# 12706.net
KiCad netlist of a schematic drawn in EAGLE
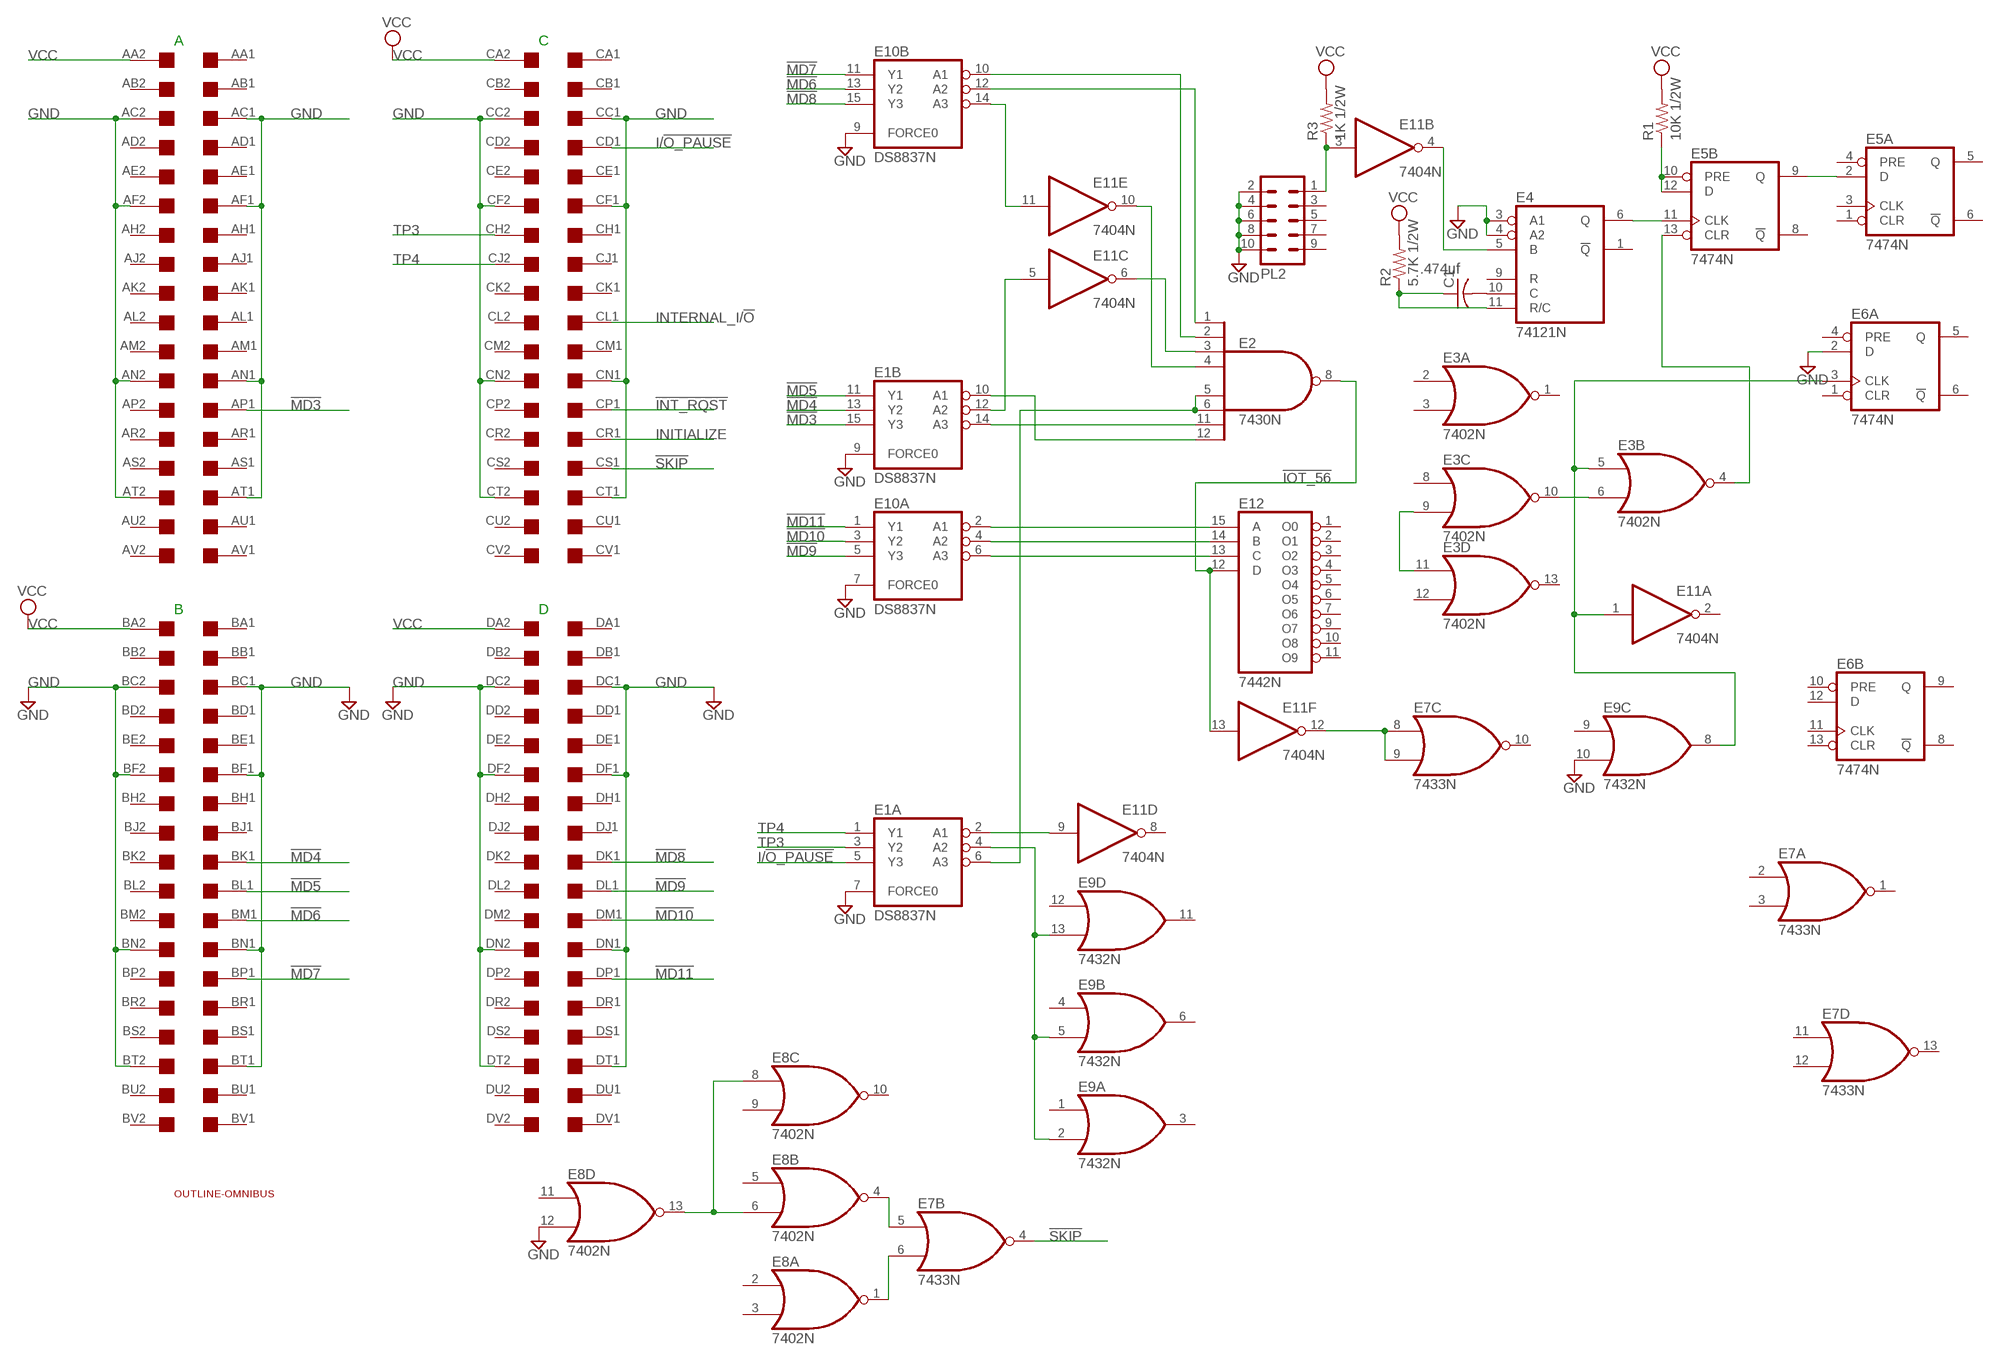
[diagram p0: schematic, sheet 1]

(export (version "E")
  (design (tool "Eeschema 10.0.6"))
  (components
    (comp (ref "C1")
      (value ".474uf")
      (footprint "eagle-import:C050-045X075")
      (libsource (lib "eagle-import") (part "C-US050-045X075"))
    )
    (comp (ref "E1")
      (value "DS8837N")
      (footprint "eagle-import:DIL16")
      (libsource (lib "eagle-import") (part "DS8837N"))
    )
    (comp (ref "E2")
      (value "7430N")
      (footprint "eagle-import:DIL14")
      (libsource (lib "eagle-import") (part "7430N"))
    )
    (comp (ref "E3")
      (value "7402N")
      (footprint "eagle-import:DIL14")
      (libsource (lib "eagle-import") (part "7402N"))
    )
    (comp (ref "E4")
      (value "74121N")
      (footprint "eagle-import:DIL14")
      (libsource (lib "eagle-import") (part "74121N"))
    )
    (comp (ref "E5")
      (value "7474N")
      (footprint "eagle-import:DIL14")
      (libsource (lib "eagle-import") (part "7474NS"))
    )
    (comp (ref "E6")
      (value "7474N")
      (footprint "eagle-import:DIL14")
      (libsource (lib "eagle-import") (part "7474NS"))
    )
    (comp (ref "E7")
      (value "7433N")
      (footprint "eagle-import:DIL14")
      (libsource (lib "eagle-import") (part "7433NLS"))
    )
    (comp (ref "E8")
      (value "7402N")
      (footprint "eagle-import:DIL14")
      (libsource (lib "eagle-import") (part "7402N"))
    )
    (comp (ref "E9")
      (value "7432N")
      (footprint "eagle-import:DIL14")
      (libsource (lib "eagle-import") (part "7432N"))
    )
    (comp (ref "E10")
      (value "DS8837N")
      (footprint "eagle-import:DIL16")
      (libsource (lib "eagle-import") (part "DS8837N"))
    )
    (comp (ref "E11")
      (value "7404N")
      (footprint "eagle-import:DIL14")
      (libsource (lib "eagle-import") (part "7404N"))
    )
    (comp (ref "E12")
      (value "7442N")
      (footprint "eagle-import:DIL16")
      (libsource (lib "eagle-import") (part "7442NLS"))
    )
    (comp (ref "PL2")
      (value "10H")
      (footprint "eagle-import:10H")
      (libsource (lib "eagle-import") (part "10H"))
    )
    (comp (ref "R1")
      (value "10K 1/2W")
      (footprint "eagle-import:0204_7")
      (libsource (lib "eagle-import") (part "R-US_0204/7"))
    )
    (comp (ref "R2")
      (value "5.7K 1/2W")
      (footprint "eagle-import:0204_7")
      (libsource (lib "eagle-import") (part "R-US_0204/7"))
    )
    (comp (ref "R3")
      (value "1K 1/2W")
      (footprint "eagle-import:0204_7")
      (libsource (lib "eagle-import") (part "R-US_0204/7"))
    )
    (comp (ref "U$1")
      (value "QUAD")
      (footprint "eagle-import:EDGE-CON8")
      (libsource (lib "eagle-import") (part "QUAD"))
    )
    (comp (ref "U$2")
      (value "OUTLINE-OMNIBUS")
      (footprint "eagle-import:OMNIBUS")
      (libsource (lib "eagle-import") (part "OUTLINE-OMNIBUS"))
    )
  )
  (nets
    (net (code "1") (name "/INITIALIZE") (class "Default")
      (node (ref "U$1") (pin "CR1") (pinfunction "1_CR1") (pintype "bidirectional"))
    )
    (net (code "2") (name "/INTERNAL_I{slash}~{O}") (class "Default")
      (node (ref "U$1") (pin "CL1") (pinfunction "1_CL1") (pintype "bidirectional"))
    )
    (net (code "3") (name "/I{slash}~{O_PAUSE}") (class "Default")
      (node (ref "E1") (pin "5") (pinfunction "Y3_5") (pintype "input"))
      (node (ref "U$1") (pin "CD1") (pinfunction "1_CD1") (pintype "bidirectional"))
    )
    (net (code "4") (name "/TP3") (class "Default")
      (node (ref "E1") (pin "3") (pinfunction "Y2_3") (pintype "input"))
      (node (ref "U$1") (pin "CH2") (pinfunction "1_CH2") (pintype "bidirectional"))
    )
    (net (code "5") (name "/TP4") (class "Default")
      (node (ref "E1") (pin "1") (pinfunction "Y1_1") (pintype "input"))
      (node (ref "U$1") (pin "CJ2") (pinfunction "1_CJ2") (pintype "bidirectional"))
    )
    (net (code "6") (name "/~{INT_RQST}") (class "Default")
      (node (ref "U$1") (pin "CP1") (pinfunction "1_CP1") (pintype "bidirectional"))
    )
    (net (code "7") (name "/~{IOT_56}") (class "Default")
      (node (ref "E11") (pin "13") (pinfunction "I_13") (pintype "input"))
      (node (ref "E12") (pin "12") (pinfunction "D_12") (pintype "input"))
      (node (ref "E2") (pin "8") (pinfunction "O_8") (pintype "output"))
    )
    (net (code "8") (name "/~{MD3}") (class "Default")
      (node (ref "E1") (pin "15") (pinfunction "Y3_15") (pintype "input"))
      (node (ref "U$1") (pin "AP1") (pinfunction "1_AP1") (pintype "bidirectional"))
    )
    (net (code "9") (name "/~{MD4}") (class "Default")
      (node (ref "E1") (pin "13") (pinfunction "Y2_13") (pintype "input"))
      (node (ref "U$1") (pin "BK1") (pinfunction "1_BK1") (pintype "bidirectional"))
    )
    (net (code "10") (name "/~{MD5}") (class "Default")
      (node (ref "E1") (pin "11") (pinfunction "Y1_11") (pintype "input"))
      (node (ref "U$1") (pin "BL1") (pinfunction "1_BL1") (pintype "bidirectional"))
    )
    (net (code "11") (name "/~{MD6}") (class "Default")
      (node (ref "E10") (pin "13") (pinfunction "Y2_13") (pintype "input"))
      (node (ref "U$1") (pin "BM1") (pinfunction "1_BM1") (pintype "bidirectional"))
    )
    (net (code "12") (name "/~{MD7}") (class "Default")
      (node (ref "E10") (pin "11") (pinfunction "Y1_11") (pintype "input"))
      (node (ref "U$1") (pin "BP1") (pinfunction "1_BP1") (pintype "bidirectional"))
    )
    (net (code "13") (name "/~{MD8}") (class "Default")
      (node (ref "E10") (pin "15") (pinfunction "Y3_15") (pintype "input"))
      (node (ref "U$1") (pin "DK1") (pinfunction "1_DK1") (pintype "bidirectional"))
    )
    (net (code "14") (name "/~{MD9}") (class "Default")
      (node (ref "E10") (pin "5") (pinfunction "Y3_5") (pintype "input"))
      (node (ref "U$1") (pin "DL1") (pinfunction "1_DL1") (pintype "bidirectional"))
    )
    (net (code "15") (name "/~{MD10}") (class "Default")
      (node (ref "E10") (pin "3") (pinfunction "Y2_3") (pintype "input"))
      (node (ref "U$1") (pin "DM1") (pinfunction "1_DM1") (pintype "bidirectional"))
    )
    (net (code "16") (name "/~{MD11}") (class "Default")
      (node (ref "E10") (pin "1") (pinfunction "Y1_1") (pintype "input"))
      (node (ref "U$1") (pin "DP1") (pinfunction "1_DP1") (pintype "bidirectional"))
    )
    (net (code "17") (name "/~{SKIP}") (class "Default")
      (node (ref "E7") (pin "4") (pinfunction "O_4") (pintype "output"))
      (node (ref "U$1") (pin "CS1") (pinfunction "1_CS1") (pintype "bidirectional"))
    )
    (net (code "18") (name "GND") (class "Default")
      (node (ref "E1") (pin "7") (pinfunction "FORCE0_7") (pintype "input"))
      (node (ref "E1") (pin "9") (pinfunction "FORCE0_9") (pintype "input"))
      (node (ref "E10") (pin "7") (pinfunction "FORCE0_7") (pintype "input"))
      (node (ref "E10") (pin "9") (pinfunction "FORCE0_9") (pintype "input"))
      (node (ref "E4") (pin "3") (pinfunction "A1_3") (pintype "input"))
      (node (ref "E4") (pin "4") (pinfunction "A2_4") (pintype "input"))
      (node (ref "E6") (pin "2") (pinfunction "D_2") (pintype "input"))
      (node (ref "E8") (pin "12") (pinfunction "I1_12") (pintype "input"))
      (node (ref "E9") (pin "10") (pinfunction "I1_10") (pintype "input"))
      (node (ref "PL2") (pin "10") (pinfunction "10_10") (pintype "passive"))
      (node (ref "PL2") (pin "2") (pinfunction "2_2") (pintype "passive"))
      (node (ref "PL2") (pin "4") (pinfunction "4_4") (pintype "passive"))
      (node (ref "PL2") (pin "6") (pinfunction "6_6") (pintype "passive"))
      (node (ref "PL2") (pin "8") (pinfunction "8_8") (pintype "passive"))
      (node (ref "U$1") (pin "AC1") (pinfunction "1_AC1") (pintype "bidirectional"))
      (node (ref "U$1") (pin "AC2") (pinfunction "1_AC2") (pintype "bidirectional"))
      (node (ref "U$1") (pin "AF1") (pinfunction "1_AF1") (pintype "bidirectional"))
      (node (ref "U$1") (pin "AF2") (pinfunction "1_AF2") (pintype "bidirectional"))
      (node (ref "U$1") (pin "AN1") (pinfunction "1_AN1") (pintype "bidirectional"))
      (node (ref "U$1") (pin "AN2") (pinfunction "1_AN2") (pintype "bidirectional"))
      (node (ref "U$1") (pin "AT1") (pinfunction "1_AT1") (pintype "bidirectional"))
      (node (ref "U$1") (pin "AT2") (pinfunction "1_AT2") (pintype "bidirectional"))
      (node (ref "U$1") (pin "BC1") (pinfunction "1_BC1") (pintype "bidirectional"))
      (node (ref "U$1") (pin "BC2") (pinfunction "1_BC2") (pintype "bidirectional"))
      (node (ref "U$1") (pin "BF1") (pinfunction "1_BF1") (pintype "bidirectional"))
      (node (ref "U$1") (pin "BF2") (pinfunction "1_BF2") (pintype "bidirectional"))
      (node (ref "U$1") (pin "BN1") (pinfunction "1_BN1") (pintype "bidirectional"))
      (node (ref "U$1") (pin "BN2") (pinfunction "1_BN2") (pintype "bidirectional"))
      (node (ref "U$1") (pin "BT1") (pinfunction "1_BT1") (pintype "bidirectional"))
      (node (ref "U$1") (pin "BT2") (pinfunction "1_BT2") (pintype "bidirectional"))
      (node (ref "U$1") (pin "CC1") (pinfunction "1_CC1") (pintype "bidirectional"))
      (node (ref "U$1") (pin "CC2") (pinfunction "1_CC2") (pintype "bidirectional"))
      (node (ref "U$1") (pin "CF1") (pinfunction "1_CF1") (pintype "bidirectional"))
      (node (ref "U$1") (pin "CF2") (pinfunction "1_CF2") (pintype "bidirectional"))
      (node (ref "U$1") (pin "CN1") (pinfunction "1_CN1") (pintype "bidirectional"))
      (node (ref "U$1") (pin "CN2") (pinfunction "1_CN2") (pintype "bidirectional"))
      (node (ref "U$1") (pin "CT1") (pinfunction "1_CT1") (pintype "bidirectional"))
      (node (ref "U$1") (pin "CT2") (pinfunction "1_CT2") (pintype "bidirectional"))
      (node (ref "U$1") (pin "DC1") (pinfunction "1_DC1") (pintype "bidirectional"))
      (node (ref "U$1") (pin "DC2") (pinfunction "1_DC2") (pintype "bidirectional"))
      (node (ref "U$1") (pin "DF1") (pinfunction "1_DF1") (pintype "bidirectional"))
      (node (ref "U$1") (pin "DF2") (pinfunction "1_DF2") (pintype "bidirectional"))
      (node (ref "U$1") (pin "DN1") (pinfunction "1_DN1") (pintype "bidirectional"))
      (node (ref "U$1") (pin "DN2") (pinfunction "1_DN2") (pintype "bidirectional"))
      (node (ref "U$1") (pin "DT1") (pinfunction "1_DT1") (pintype "bidirectional"))
      (node (ref "U$1") (pin "DT2") (pinfunction "1_DT2") (pintype "bidirectional"))
    )
    (net (code "19") (name "Net-(E1A-A2)") (class "Default")
      (node (ref "E1") (pin "4") (pinfunction "A2_4") (pintype "output"))
      (node (ref "E9") (pin "13") (pinfunction "I1_13") (pintype "input"))
      (node (ref "E9") (pin "2") (pinfunction "I1_2") (pintype "input"))
      (node (ref "E9") (pin "5") (pinfunction "I1_5") (pintype "input"))
    )
    (net (code "20") (name "Net-(E1A-A3)") (class "Default")
      (node (ref "E1") (pin "6") (pinfunction "A3_6") (pintype "output"))
      (node (ref "E2") (pin "5") (pinfunction "I4_5") (pintype "input"))
      (node (ref "E2") (pin "6") (pinfunction "I5_6") (pintype "input"))
    )
    (net (code "21") (name "Net-(E1B-A1)") (class "Default")
      (node (ref "E1") (pin "10") (pinfunction "A1_10") (pintype "output"))
      (node (ref "E2") (pin "12") (pinfunction "I7_12") (pintype "input"))
    )
    (net (code "22") (name "Net-(E1B-A3)") (class "Default")
      (node (ref "E1") (pin "14") (pinfunction "A3_14") (pintype "output"))
      (node (ref "E2") (pin "11") (pinfunction "I6_11") (pintype "input"))
    )
    (net (code "23") (name "Net-(E3B-I1)") (class "Default")
      (node (ref "E3") (pin "10") (pinfunction "O_10") (pintype "output"))
      (node (ref "E3") (pin "6") (pinfunction "I1_6") (pintype "input"))
    )
    (net (code "24") (name "Net-(E3B-O)") (class "Default")
      (node (ref "E3") (pin "4") (pinfunction "O_4") (pintype "output"))
      (node (ref "E5") (pin "13") (pinfunction "CLR_13") (pintype "input"))
    )
    (net (code "25") (name "Net-(E3C-I1)") (class "Default")
      (node (ref "E3") (pin "11") (pinfunction "I0_11") (pintype "input"))
      (node (ref "E3") (pin "9") (pinfunction "I1_9") (pintype "input"))
    )
    (net (code "26") (name "Net-(E4A-C)") (class "Default")
      (node (ref "C1") (pin "2") (pinfunction "2_2") (pintype "passive"))
      (node (ref "E4") (pin "10") (pinfunction "C_10") (pintype "input"))
    )
    (net (code "27") (name "Net-(E4A-Q)") (class "Default")
      (node (ref "E4") (pin "6") (pinfunction "Q_6") (pintype "output"))
      (node (ref "E5") (pin "11") (pinfunction "CLK_11") (pintype "input"))
    )
    (net (code "28") (name "Net-(E4A-R{slash}C)") (class "Default")
      (node (ref "C1") (pin "1") (pinfunction "1_1") (pintype "passive"))
      (node (ref "E4") (pin "11") (pinfunction "R/C_11") (pintype "input"))
      (node (ref "R2") (pin "1") (pinfunction "1_1") (pintype "passive"))
    )
    (net (code "29") (name "Net-(E5A-D)") (class "Default")
      (node (ref "E5") (pin "2") (pinfunction "D_2") (pintype "input"))
      (node (ref "E5") (pin "9") (pinfunction "Q_9") (pintype "output"))
    )
    (net (code "30") (name "Net-(E5B-D)") (class "Default")
      (node (ref "E5") (pin "10") (pinfunction "PRE_10") (pintype "input"))
      (node (ref "E5") (pin "12") (pinfunction "D_12") (pintype "input"))
      (node (ref "R1") (pin "1") (pinfunction "1_1") (pintype "passive"))
    )
    (net (code "31") (name "Net-(E7B-I0)") (class "Default")
      (node (ref "E7") (pin "5") (pinfunction "I0_5") (pintype "input"))
      (node (ref "E8") (pin "4") (pinfunction "O_4") (pintype "output"))
    )
    (net (code "32") (name "Net-(E7B-I1)") (class "Default")
      (node (ref "E7") (pin "6") (pinfunction "I1_6") (pintype "input"))
      (node (ref "E8") (pin "1") (pinfunction "O_1") (pintype "output"))
    )
    (net (code "33") (name "Net-(E8B-I1)") (class "Default")
      (node (ref "E8") (pin "13") (pinfunction "O_13") (pintype "output"))
      (node (ref "E8") (pin "6") (pinfunction "I1_6") (pintype "input"))
      (node (ref "E8") (pin "8") (pinfunction "I0_8") (pintype "input"))
    )
    (net (code "34") (name "Net-(E10A-A1)") (class "Default")
      (node (ref "E10") (pin "2") (pinfunction "A1_2") (pintype "output"))
      (node (ref "E12") (pin "15") (pinfunction "A_15") (pintype "input"))
    )
    (net (code "35") (name "Net-(E10A-A2)") (class "Default")
      (node (ref "E10") (pin "4") (pinfunction "A2_4") (pintype "output"))
      (node (ref "E12") (pin "14") (pinfunction "B_14") (pintype "input"))
    )
    (net (code "36") (name "Net-(E10A-A3)") (class "Default")
      (node (ref "E10") (pin "6") (pinfunction "A3_6") (pintype "output"))
      (node (ref "E12") (pin "13") (pinfunction "C_13") (pintype "input"))
    )
    (net (code "37") (name "Net-(E10B-A1)") (class "Default")
      (node (ref "E10") (pin "10") (pinfunction "A1_10") (pintype "output"))
      (node (ref "E2") (pin "2") (pinfunction "I1_2") (pintype "input"))
    )
    (net (code "38") (name "Net-(E10B-A2)") (class "Default")
      (node (ref "E10") (pin "12") (pinfunction "A2_12") (pintype "output"))
      (node (ref "E2") (pin "1") (pinfunction "I0_1") (pintype "input"))
    )
    (net (code "39") (name "Net-(E10B-A3)") (class "Default")
      (node (ref "E10") (pin "14") (pinfunction "A3_14") (pintype "output"))
      (node (ref "E11") (pin "11") (pinfunction "I_11") (pintype "input"))
    )
    (net (code "40") (name "Net-(E11A-I)") (class "Default")
      (node (ref "E11") (pin "1") (pinfunction "I_1") (pintype "input"))
      (node (ref "E3") (pin "5") (pinfunction "I0_5") (pintype "input"))
      (node (ref "E6") (pin "3") (pinfunction "CLK_3") (pintype "input"))
      (node (ref "E9") (pin "8") (pinfunction "O_8") (pintype "output"))
    )
    (net (code "41") (name "Net-(E11B-I)") (class "Default")
      (node (ref "E11") (pin "3") (pinfunction "I_3") (pintype "input"))
      (node (ref "PL2") (pin "1") (pinfunction "1_1") (pintype "passive"))
      (node (ref "R3") (pin "1") (pinfunction "1_1") (pintype "passive"))
    )
    (net (code "42") (name "Net-(E11B-O)") (class "Default")
      (node (ref "E11") (pin "4") (pinfunction "O_4") (pintype "output"))
      (node (ref "E4") (pin "5") (pinfunction "B_5") (pintype "input"))
    )
    (net (code "43") (name "Net-(E11C-I)") (class "Default")
      (node (ref "E1") (pin "12") (pinfunction "A2_12") (pintype "output"))
      (node (ref "E11") (pin "5") (pinfunction "I_5") (pintype "input"))
    )
    (net (code "44") (name "Net-(E11C-O)") (class "Default")
      (node (ref "E11") (pin "6") (pinfunction "O_6") (pintype "output"))
      (node (ref "E2") (pin "3") (pinfunction "I2_3") (pintype "input"))
    )
    (net (code "45") (name "Net-(E11D-I)") (class "Default")
      (node (ref "E1") (pin "2") (pinfunction "A1_2") (pintype "output"))
      (node (ref "E11") (pin "9") (pinfunction "I_9") (pintype "input"))
    )
    (net (code "46") (name "Net-(E11E-O)") (class "Default")
      (node (ref "E11") (pin "10") (pinfunction "O_10") (pintype "output"))
      (node (ref "E2") (pin "4") (pinfunction "I3_4") (pintype "input"))
    )
    (net (code "47") (name "Net-(E11F-O)") (class "Default")
      (node (ref "E11") (pin "12") (pinfunction "O_12") (pintype "output"))
      (node (ref "E7") (pin "8") (pinfunction "I0_8") (pintype "input"))
      (node (ref "E7") (pin "9") (pinfunction "I1_9") (pintype "input"))
    )
    (net (code "48") (name "VCC") (class "Default")
      (node (ref "R1") (pin "2") (pinfunction "2_2") (pintype "passive"))
      (node (ref "R2") (pin "2") (pinfunction "2_2") (pintype "passive"))
      (node (ref "R3") (pin "2") (pinfunction "2_2") (pintype "passive"))
      (node (ref "U$1") (pin "AA2") (pinfunction "1_AA2") (pintype "bidirectional"))
      (node (ref "U$1") (pin "BA2") (pinfunction "1_BA2") (pintype "bidirectional"))
      (node (ref "U$1") (pin "CA2") (pinfunction "1_CA2") (pintype "bidirectional"))
      (node (ref "U$1") (pin "DA2") (pinfunction "1_DA2") (pintype "bidirectional"))
    )
    (net (code "49") (name "unconnected-(E3A-I0-Pad2)") (class "Default")
      (node (ref "E3") (pin "2") (pinfunction "I0_2") (pintype "input"))
    )
    (net (code "50") (name "unconnected-(E3A-I1-Pad3)") (class "Default")
      (node (ref "E3") (pin "3") (pinfunction "I1_3") (pintype "input"))
    )
    (net (code "51") (name "unconnected-(E3A-O-Pad1)") (class "Default")
      (node (ref "E3") (pin "1") (pinfunction "O_1") (pintype "output"))
    )
    (net (code "52") (name "unconnected-(E3C-I0-Pad8)") (class "Default")
      (node (ref "E3") (pin "8") (pinfunction "I0_8") (pintype "input"))
    )
    (net (code "53") (name "unconnected-(E3D-I1-Pad12)") (class "Default")
      (node (ref "E3") (pin "12") (pinfunction "I1_12") (pintype "input"))
    )
    (net (code "54") (name "unconnected-(E3D-O-Pad13)") (class "Default")
      (node (ref "E3") (pin "13") (pinfunction "O_13") (pintype "output"))
    )
    (net (code "55") (name "unconnected-(E4A-R-Pad9)") (class "Default")
      (node (ref "E4") (pin "9") (pinfunction "R_9") (pintype "input"))
    )
    (net (code "56") (name "unconnected-(E4A-~{Q}-Pad1)") (class "Default")
      (node (ref "E4") (pin "1") (pinfunction "~{Q}_1") (pintype "output"))
    )
    (net (code "57") (name "unconnected-(E5A-CLK-Pad3)") (class "Default")
      (node (ref "E5") (pin "3") (pinfunction "CLK_3") (pintype "input"))
    )
    (net (code "58") (name "unconnected-(E5A-CLR-Pad1)") (class "Default")
      (node (ref "E5") (pin "1") (pinfunction "CLR_1") (pintype "input"))
    )
    (net (code "59") (name "unconnected-(E5A-PRE-Pad4)") (class "Default")
      (node (ref "E5") (pin "4") (pinfunction "PRE_4") (pintype "input"))
    )
    (net (code "60") (name "unconnected-(E5A-Q-Pad5)") (class "Default")
      (node (ref "E5") (pin "5") (pinfunction "Q_5") (pintype "output"))
    )
    (net (code "61") (name "unconnected-(E5A-~{Q}-Pad6)") (class "Default")
      (node (ref "E5") (pin "6") (pinfunction "~{Q}_6") (pintype "output"))
    )
    (net (code "62") (name "unconnected-(E5B-~{Q}-Pad8)") (class "Default")
      (node (ref "E5") (pin "8") (pinfunction "~{Q}_8") (pintype "output"))
    )
    (net (code "63") (name "unconnected-(E6A-CLR-Pad1)") (class "Default")
      (node (ref "E6") (pin "1") (pinfunction "CLR_1") (pintype "input"))
    )
    (net (code "64") (name "unconnected-(E6A-PRE-Pad4)") (class "Default")
      (node (ref "E6") (pin "4") (pinfunction "PRE_4") (pintype "input"))
    )
    (net (code "65") (name "unconnected-(E6A-Q-Pad5)") (class "Default")
      (node (ref "E6") (pin "5") (pinfunction "Q_5") (pintype "output"))
    )
    (net (code "66") (name "unconnected-(E6A-~{Q}-Pad6)") (class "Default")
      (node (ref "E6") (pin "6") (pinfunction "~{Q}_6") (pintype "output"))
    )
    (net (code "67") (name "unconnected-(E6B-CLK-Pad11)") (class "Default")
      (node (ref "E6") (pin "11") (pinfunction "CLK_11") (pintype "input"))
    )
    (net (code "68") (name "unconnected-(E6B-CLR-Pad13)") (class "Default")
      (node (ref "E6") (pin "13") (pinfunction "CLR_13") (pintype "input"))
    )
    (net (code "69") (name "unconnected-(E6B-D-Pad12)") (class "Default")
      (node (ref "E6") (pin "12") (pinfunction "D_12") (pintype "input"))
    )
    (net (code "70") (name "unconnected-(E6B-PRE-Pad10)") (class "Default")
      (node (ref "E6") (pin "10") (pinfunction "PRE_10") (pintype "input"))
    )
    (net (code "71") (name "unconnected-(E6B-Q-Pad9)") (class "Default")
      (node (ref "E6") (pin "9") (pinfunction "Q_9") (pintype "output"))
    )
    (net (code "72") (name "unconnected-(E6B-~{Q}-Pad8)") (class "Default")
      (node (ref "E6") (pin "8") (pinfunction "~{Q}_8") (pintype "output"))
    )
    (net (code "73") (name "unconnected-(E7A-I0-Pad2)") (class "Default")
      (node (ref "E7") (pin "2") (pinfunction "I0_2") (pintype "input"))
    )
    (net (code "74") (name "unconnected-(E7A-I1-Pad3)") (class "Default")
      (node (ref "E7") (pin "3") (pinfunction "I1_3") (pintype "input"))
    )
    (net (code "75") (name "unconnected-(E7A-O-Pad1)") (class "Default")
      (node (ref "E7") (pin "1") (pinfunction "O_1") (pintype "output"))
    )
    (net (code "76") (name "unconnected-(E7C-O-Pad10)") (class "Default")
      (node (ref "E7") (pin "10") (pinfunction "O_10") (pintype "output"))
    )
    (net (code "77") (name "unconnected-(E7D-I0-Pad11)") (class "Default")
      (node (ref "E7") (pin "11") (pinfunction "I0_11") (pintype "input"))
    )
    (net (code "78") (name "unconnected-(E7D-I1-Pad12)") (class "Default")
      (node (ref "E7") (pin "12") (pinfunction "I1_12") (pintype "input"))
    )
    (net (code "79") (name "unconnected-(E7D-O-Pad13)") (class "Default")
      (node (ref "E7") (pin "13") (pinfunction "O_13") (pintype "output"))
    )
    (net (code "80") (name "unconnected-(E8A-I0-Pad2)") (class "Default")
      (node (ref "E8") (pin "2") (pinfunction "I0_2") (pintype "input"))
    )
    (net (code "81") (name "unconnected-(E8A-I1-Pad3)") (class "Default")
      (node (ref "E8") (pin "3") (pinfunction "I1_3") (pintype "input"))
    )
    (net (code "82") (name "unconnected-(E8B-I0-Pad5)") (class "Default")
      (node (ref "E8") (pin "5") (pinfunction "I0_5") (pintype "input"))
    )
    (net (code "83") (name "unconnected-(E8C-I1-Pad9)") (class "Default")
      (node (ref "E8") (pin "9") (pinfunction "I1_9") (pintype "input"))
    )
    (net (code "84") (name "unconnected-(E8C-O-Pad10)") (class "Default")
      (node (ref "E8") (pin "10") (pinfunction "O_10") (pintype "output"))
    )
    (net (code "85") (name "unconnected-(E8D-I0-Pad11)") (class "Default")
      (node (ref "E8") (pin "11") (pinfunction "I0_11") (pintype "input"))
    )
    (net (code "86") (name "unconnected-(E9A-I0-Pad1)") (class "Default")
      (node (ref "E9") (pin "1") (pinfunction "I0_1") (pintype "input"))
    )
    (net (code "87") (name "unconnected-(E9A-O-Pad3)") (class "Default")
      (node (ref "E9") (pin "3") (pinfunction "O_3") (pintype "output"))
    )
    (net (code "88") (name "unconnected-(E9B-I0-Pad4)") (class "Default")
      (node (ref "E9") (pin "4") (pinfunction "I0_4") (pintype "input"))
    )
    (net (code "89") (name "unconnected-(E9B-O-Pad6)") (class "Default")
      (node (ref "E9") (pin "6") (pinfunction "O_6") (pintype "output"))
    )
    (net (code "90") (name "unconnected-(E9C-I0-Pad9)") (class "Default")
      (node (ref "E9") (pin "9") (pinfunction "I0_9") (pintype "input"))
    )
    (net (code "91") (name "unconnected-(E9D-I0-Pad12)") (class "Default")
      (node (ref "E9") (pin "12") (pinfunction "I0_12") (pintype "input"))
    )
    (net (code "92") (name "unconnected-(E9D-O-Pad11)") (class "Default")
      (node (ref "E9") (pin "11") (pinfunction "O_11") (pintype "output"))
    )
    (net (code "93") (name "unconnected-(E11A-O-Pad2)") (class "Default")
      (node (ref "E11") (pin "2") (pinfunction "O_2") (pintype "output"))
    )
    (net (code "94") (name "unconnected-(E11D-O-Pad8)") (class "Default")
      (node (ref "E11") (pin "8") (pinfunction "O_8") (pintype "output"))
    )
    (net (code "95") (name "unconnected-(E12A-O0-Pad1)") (class "Default")
      (node (ref "E12") (pin "1") (pinfunction "O0_1") (pintype "output"))
    )
    (net (code "96") (name "unconnected-(E12A-O1-Pad2)") (class "Default")
      (node (ref "E12") (pin "2") (pinfunction "O1_2") (pintype "output"))
    )
    (net (code "97") (name "unconnected-(E12A-O2-Pad3)") (class "Default")
      (node (ref "E12") (pin "3") (pinfunction "O2_3") (pintype "output"))
    )
    (net (code "98") (name "unconnected-(E12A-O3-Pad4)") (class "Default")
      (node (ref "E12") (pin "4") (pinfunction "O3_4") (pintype "output"))
    )
    (net (code "99") (name "unconnected-(E12A-O4-Pad5)") (class "Default")
      (node (ref "E12") (pin "5") (pinfunction "O4_5") (pintype "output"))
    )
    (net (code "100") (name "unconnected-(E12A-O5-Pad6)") (class "Default")
      (node (ref "E12") (pin "6") (pinfunction "O5_6") (pintype "output"))
    )
    (net (code "101") (name "unconnected-(E12A-O6-Pad7)") (class "Default")
      (node (ref "E12") (pin "7") (pinfunction "O6_7") (pintype "output"))
    )
    (net (code "102") (name "unconnected-(E12A-O7-Pad9)") (class "Default")
      (node (ref "E12") (pin "9") (pinfunction "O7_9") (pintype "output"))
    )
    (net (code "103") (name "unconnected-(E12A-O8-Pad10)") (class "Default")
      (node (ref "E12") (pin "10") (pinfunction "O8_10") (pintype "output"))
    )
    (net (code "104") (name "unconnected-(E12A-O9-Pad11)") (class "Default")
      (node (ref "E12") (pin "11") (pinfunction "O9_11") (pintype "output"))
    )
    (net (code "105") (name "unconnected-(PL2-Pad3)") (class "Default")
      (node (ref "PL2") (pin "3") (pinfunction "3_3") (pintype "passive"))
    )
    (net (code "106") (name "unconnected-(PL2-Pad5)") (class "Default")
      (node (ref "PL2") (pin "5") (pinfunction "5_5") (pintype "passive"))
    )
    (net (code "107") (name "unconnected-(PL2-Pad7)") (class "Default")
      (node (ref "PL2") (pin "7") (pinfunction "7_7") (pintype "passive"))
    )
    (net (code "108") (name "unconnected-(PL2-Pad9)") (class "Default")
      (node (ref "PL2") (pin "9") (pinfunction "9_9") (pintype "passive"))
    )
    (net (code "109") (name "unconnected-(U$1A-1-PadAA1)") (class "Default")
      (node (ref "U$1") (pin "AA1") (pinfunction "1_AA1") (pintype "bidirectional"))
    )
    (net (code "110") (name "unconnected-(U$1AA-1-PadAR1)") (class "Default")
      (node (ref "U$1") (pin "AR1") (pinfunction "1_AR1") (pintype "bidirectional"))
    )
    (net (code "111") (name "unconnected-(U$1AB-1-PadAR2)") (class "Default")
      (node (ref "U$1") (pin "AR2") (pinfunction "1_AR2") (pintype "bidirectional"))
    )
    (net (code "112") (name "unconnected-(U$1AC-1-PadAS1)") (class "Default")
      (node (ref "U$1") (pin "AS1") (pinfunction "1_AS1") (pintype "bidirectional"))
    )
    (net (code "113") (name "unconnected-(U$1AD-1-PadAS2)") (class "Default")
      (node (ref "U$1") (pin "AS2") (pinfunction "1_AS2") (pintype "bidirectional"))
    )
    (net (code "114") (name "unconnected-(U$1AG-1-PadAU1)") (class "Default")
      (node (ref "U$1") (pin "AU1") (pinfunction "1_AU1") (pintype "bidirectional"))
    )
    (net (code "115") (name "unconnected-(U$1AH-1-PadAU2)") (class "Default")
      (node (ref "U$1") (pin "AU2") (pinfunction "1_AU2") (pintype "bidirectional"))
    )
    (net (code "116") (name "unconnected-(U$1AI-1-PadAV1)") (class "Default")
      (node (ref "U$1") (pin "AV1") (pinfunction "1_AV1") (pintype "bidirectional"))
    )
    (net (code "117") (name "unconnected-(U$1AJ-1-PadAV2)") (class "Default")
      (node (ref "U$1") (pin "AV2") (pinfunction "1_AV2") (pintype "bidirectional"))
    )
    (net (code "118") (name "unconnected-(U$1AK-1-PadBA1)") (class "Default")
      (node (ref "U$1") (pin "BA1") (pinfunction "1_BA1") (pintype "bidirectional"))
    )
    (net (code "119") (name "unconnected-(U$1AM-1-PadBB1)") (class "Default")
      (node (ref "U$1") (pin "BB1") (pinfunction "1_BB1") (pintype "bidirectional"))
    )
    (net (code "120") (name "unconnected-(U$1AN-1-PadBB2)") (class "Default")
      (node (ref "U$1") (pin "BB2") (pinfunction "1_BB2") (pintype "bidirectional"))
    )
    (net (code "121") (name "unconnected-(U$1AQ-1-PadBD1)") (class "Default")
      (node (ref "U$1") (pin "BD1") (pinfunction "1_BD1") (pintype "bidirectional"))
    )
    (net (code "122") (name "unconnected-(U$1AR-1-PadBD2)") (class "Default")
      (node (ref "U$1") (pin "BD2") (pinfunction "1_BD2") (pintype "bidirectional"))
    )
    (net (code "123") (name "unconnected-(U$1AS-1-PadBE1)") (class "Default")
      (node (ref "U$1") (pin "BE1") (pinfunction "1_BE1") (pintype "bidirectional"))
    )
    (net (code "124") (name "unconnected-(U$1AT-1-PadBE2)") (class "Default")
      (node (ref "U$1") (pin "BE2") (pinfunction "1_BE2") (pintype "bidirectional"))
    )
    (net (code "125") (name "unconnected-(U$1AW-1-PadBH1)") (class "Default")
      (node (ref "U$1") (pin "BH1") (pinfunction "1_BH1") (pintype "bidirectional"))
    )
    (net (code "126") (name "unconnected-(U$1AX-1-PadBH2)") (class "Default")
      (node (ref "U$1") (pin "BH2") (pinfunction "1_BH2") (pintype "bidirectional"))
    )
    (net (code "127") (name "unconnected-(U$1AY-1-PadBJ1)") (class "Default")
      (node (ref "U$1") (pin "BJ1") (pinfunction "1_BJ1") (pintype "bidirectional"))
    )
    (net (code "128") (name "unconnected-(U$1AZ-1-PadBJ2)") (class "Default")
      (node (ref "U$1") (pin "BJ2") (pinfunction "1_BJ2") (pintype "bidirectional"))
    )
    (net (code "129") (name "unconnected-(U$1BB-1-PadBK2)") (class "Default")
      (node (ref "U$1") (pin "BK2") (pinfunction "1_BK2") (pintype "bidirectional"))
    )
    (net (code "130") (name "unconnected-(U$1BD-1-PadBL2)") (class "Default")
      (node (ref "U$1") (pin "BL2") (pinfunction "1_BL2") (pintype "bidirectional"))
    )
    (net (code "131") (name "unconnected-(U$1BF-1-PadBM2)") (class "Default")
      (node (ref "U$1") (pin "BM2") (pinfunction "1_BM2") (pintype "bidirectional"))
    )
    (net (code "132") (name "unconnected-(U$1BJ-1-PadBP2)") (class "Default")
      (node (ref "U$1") (pin "BP2") (pinfunction "1_BP2") (pintype "bidirectional"))
    )
    (net (code "133") (name "unconnected-(U$1BK-1-PadBR1)") (class "Default")
      (node (ref "U$1") (pin "BR1") (pinfunction "1_BR1") (pintype "bidirectional"))
    )
    (net (code "134") (name "unconnected-(U$1BL-1-PadBR2)") (class "Default")
      (node (ref "U$1") (pin "BR2") (pinfunction "1_BR2") (pintype "bidirectional"))
    )
    (net (code "135") (name "unconnected-(U$1BM-1-PadBS1)") (class "Default")
      (node (ref "U$1") (pin "BS1") (pinfunction "1_BS1") (pintype "bidirectional"))
    )
    (net (code "136") (name "unconnected-(U$1BN-1-PadBS2)") (class "Default")
      (node (ref "U$1") (pin "BS2") (pinfunction "1_BS2") (pintype "bidirectional"))
    )
    (net (code "137") (name "unconnected-(U$1BQ-1-PadBU1)") (class "Default")
      (node (ref "U$1") (pin "BU1") (pinfunction "1_BU1") (pintype "bidirectional"))
    )
    (net (code "138") (name "unconnected-(U$1BR-1-PadBU2)") (class "Default")
      (node (ref "U$1") (pin "BU2") (pinfunction "1_BU2") (pintype "bidirectional"))
    )
    (net (code "139") (name "unconnected-(U$1BS-1-PadBV1)") (class "Default")
      (node (ref "U$1") (pin "BV1") (pinfunction "1_BV1") (pintype "bidirectional"))
    )
    (net (code "140") (name "unconnected-(U$1BT-1-PadBV2)") (class "Default")
      (node (ref "U$1") (pin "BV2") (pinfunction "1_BV2") (pintype "bidirectional"))
    )
    (net (code "141") (name "unconnected-(U$1BU-1-PadCA1)") (class "Default")
      (node (ref "U$1") (pin "CA1") (pinfunction "1_CA1") (pintype "bidirectional"))
    )
    (net (code "142") (name "unconnected-(U$1BW-1-PadCB1)") (class "Default")
      (node (ref "U$1") (pin "CB1") (pinfunction "1_CB1") (pintype "bidirectional"))
    )
    (net (code "143") (name "unconnected-(U$1BX-1-PadCB2)") (class "Default")
      (node (ref "U$1") (pin "CB2") (pinfunction "1_CB2") (pintype "bidirectional"))
    )
    (net (code "144") (name "unconnected-(U$1C-1-PadAB1)") (class "Default")
      (node (ref "U$1") (pin "AB1") (pinfunction "1_AB1") (pintype "bidirectional"))
    )
    (net (code "145") (name "unconnected-(U$1CB-1-PadCD2)") (class "Default")
      (node (ref "U$1") (pin "CD2") (pinfunction "1_CD2") (pintype "bidirectional"))
    )
    (net (code "146") (name "unconnected-(U$1CC-1-PadCE1)") (class "Default")
      (node (ref "U$1") (pin "CE1") (pinfunction "1_CE1") (pintype "bidirectional"))
    )
    (net (code "147") (name "unconnected-(U$1CD-1-PadCE2)") (class "Default")
      (node (ref "U$1") (pin "CE2") (pinfunction "1_CE2") (pintype "bidirectional"))
    )
    (net (code "148") (name "unconnected-(U$1CG-1-PadCH1)") (class "Default")
      (node (ref "U$1") (pin "CH1") (pinfunction "1_CH1") (pintype "bidirectional"))
    )
    (net (code "149") (name "unconnected-(U$1CI-1-PadCJ1)") (class "Default")
      (node (ref "U$1") (pin "CJ1") (pinfunction "1_CJ1") (pintype "bidirectional"))
    )
    (net (code "150") (name "unconnected-(U$1CK-1-PadCK1)") (class "Default")
      (node (ref "U$1") (pin "CK1") (pinfunction "1_CK1") (pintype "bidirectional"))
    )
    (net (code "151") (name "unconnected-(U$1CL-1-PadCK2)") (class "Default")
      (node (ref "U$1") (pin "CK2") (pinfunction "1_CK2") (pintype "bidirectional"))
    )
    (net (code "152") (name "unconnected-(U$1CN-1-PadCL2)") (class "Default")
      (node (ref "U$1") (pin "CL2") (pinfunction "1_CL2") (pintype "bidirectional"))
    )
    (net (code "153") (name "unconnected-(U$1CO-1-PadCM1)") (class "Default")
      (node (ref "U$1") (pin "CM1") (pinfunction "1_CM1") (pintype "bidirectional"))
    )
    (net (code "154") (name "unconnected-(U$1CP-1-PadCM2)") (class "Default")
      (node (ref "U$1") (pin "CM2") (pinfunction "1_CM2") (pintype "bidirectional"))
    )
    (net (code "155") (name "unconnected-(U$1CT-1-PadCP2)") (class "Default")
      (node (ref "U$1") (pin "CP2") (pinfunction "1_CP2") (pintype "bidirectional"))
    )
    (net (code "156") (name "unconnected-(U$1CV-1-PadCR2)") (class "Default")
      (node (ref "U$1") (pin "CR2") (pinfunction "1_CR2") (pintype "bidirectional"))
    )
    (net (code "157") (name "unconnected-(U$1CX-1-PadCS2)") (class "Default")
      (node (ref "U$1") (pin "CS2") (pinfunction "1_CS2") (pintype "bidirectional"))
    )
    (net (code "158") (name "unconnected-(U$1D-1-PadAB2)") (class "Default")
      (node (ref "U$1") (pin "AB2") (pinfunction "1_AB2") (pintype "bidirectional"))
    )
    (net (code "159") (name "unconnected-(U$1DA-1-PadCU1)") (class "Default")
      (node (ref "U$1") (pin "CU1") (pinfunction "1_CU1") (pintype "bidirectional"))
    )
    (net (code "160") (name "unconnected-(U$1DB-1-PadCU2)") (class "Default")
      (node (ref "U$1") (pin "CU2") (pinfunction "1_CU2") (pintype "bidirectional"))
    )
    (net (code "161") (name "unconnected-(U$1DC-1-PadCV1)") (class "Default")
      (node (ref "U$1") (pin "CV1") (pinfunction "1_CV1") (pintype "bidirectional"))
    )
    (net (code "162") (name "unconnected-(U$1DD-1-PadCV2)") (class "Default")
      (node (ref "U$1") (pin "CV2") (pinfunction "1_CV2") (pintype "bidirectional"))
    )
    (net (code "163") (name "unconnected-(U$1DE-1-PadDA1)") (class "Default")
      (node (ref "U$1") (pin "DA1") (pinfunction "1_DA1") (pintype "bidirectional"))
    )
    (net (code "164") (name "unconnected-(U$1DG-1-PadDB1)") (class "Default")
      (node (ref "U$1") (pin "DB1") (pinfunction "1_DB1") (pintype "bidirectional"))
    )
    (net (code "165") (name "unconnected-(U$1DH-1-PadDB2)") (class "Default")
      (node (ref "U$1") (pin "DB2") (pinfunction "1_DB2") (pintype "bidirectional"))
    )
    (net (code "166") (name "unconnected-(U$1DK-1-PadDD1)") (class "Default")
      (node (ref "U$1") (pin "DD1") (pinfunction "1_DD1") (pintype "bidirectional"))
    )
    (net (code "167") (name "unconnected-(U$1DL-1-PadDD2)") (class "Default")
      (node (ref "U$1") (pin "DD2") (pinfunction "1_DD2") (pintype "bidirectional"))
    )
    (net (code "168") (name "unconnected-(U$1DM-1-PadDE1)") (class "Default")
      (node (ref "U$1") (pin "DE1") (pinfunction "1_DE1") (pintype "bidirectional"))
    )
    (net (code "169") (name "unconnected-(U$1DN-1-PadDE2)") (class "Default")
      (node (ref "U$1") (pin "DE2") (pinfunction "1_DE2") (pintype "bidirectional"))
    )
    (net (code "170") (name "unconnected-(U$1DQ-1-PadDH1)") (class "Default")
      (node (ref "U$1") (pin "DH1") (pinfunction "1_DH1") (pintype "bidirectional"))
    )
    (net (code "171") (name "unconnected-(U$1DR-1-PadDH2)") (class "Default")
      (node (ref "U$1") (pin "DH2") (pinfunction "1_DH2") (pintype "bidirectional"))
    )
    (net (code "172") (name "unconnected-(U$1DS-1-PadDJ1)") (class "Default")
      (node (ref "U$1") (pin "DJ1") (pinfunction "1_DJ1") (pintype "bidirectional"))
    )
    (net (code "173") (name "unconnected-(U$1DT-1-PadDJ2)") (class "Default")
      (node (ref "U$1") (pin "DJ2") (pinfunction "1_DJ2") (pintype "bidirectional"))
    )
    (net (code "174") (name "unconnected-(U$1DV-1-PadDK2)") (class "Default")
      (node (ref "U$1") (pin "DK2") (pinfunction "1_DK2") (pintype "bidirectional"))
    )
    (net (code "175") (name "unconnected-(U$1DX-1-PadDL2)") (class "Default")
      (node (ref "U$1") (pin "DL2") (pinfunction "1_DL2") (pintype "bidirectional"))
    )
    (net (code "176") (name "unconnected-(U$1DZ-1-PadDM2)") (class "Default")
      (node (ref "U$1") (pin "DM2") (pinfunction "1_DM2") (pintype "bidirectional"))
    )
    (net (code "177") (name "unconnected-(U$1ED-1-PadDP2)") (class "Default")
      (node (ref "U$1") (pin "DP2") (pinfunction "1_DP2") (pintype "bidirectional"))
    )
    (net (code "178") (name "unconnected-(U$1EE-1-PadDR1)") (class "Default")
      (node (ref "U$1") (pin "DR1") (pinfunction "1_DR1") (pintype "bidirectional"))
    )
    (net (code "179") (name "unconnected-(U$1EF-1-PadDR2)") (class "Default")
      (node (ref "U$1") (pin "DR2") (pinfunction "1_DR2") (pintype "bidirectional"))
    )
    (net (code "180") (name "unconnected-(U$1EG-1-PadDS1)") (class "Default")
      (node (ref "U$1") (pin "DS1") (pinfunction "1_DS1") (pintype "bidirectional"))
    )
    (net (code "181") (name "unconnected-(U$1EH-1-PadDS2)") (class "Default")
      (node (ref "U$1") (pin "DS2") (pinfunction "1_DS2") (pintype "bidirectional"))
    )
    (net (code "182") (name "unconnected-(U$1EK-1-PadDU1)") (class "Default")
      (node (ref "U$1") (pin "DU1") (pinfunction "1_DU1") (pintype "bidirectional"))
    )
    (net (code "183") (name "unconnected-(U$1EL-1-PadDU2)") (class "Default")
      (node (ref "U$1") (pin "DU2") (pinfunction "1_DU2") (pintype "bidirectional"))
    )
    (net (code "184") (name "unconnected-(U$1EM-1-PadDV1)") (class "Default")
      (node (ref "U$1") (pin "DV1") (pinfunction "1_DV1") (pintype "bidirectional"))
    )
    (net (code "185") (name "unconnected-(U$1EN-1-PadDV2)") (class "Default")
      (node (ref "U$1") (pin "DV2") (pinfunction "1_DV2") (pintype "bidirectional"))
    )
    (net (code "186") (name "unconnected-(U$1G-1-PadAD1)") (class "Default")
      (node (ref "U$1") (pin "AD1") (pinfunction "1_AD1") (pintype "bidirectional"))
    )
    (net (code "187") (name "unconnected-(U$1H-1-PadAD2)") (class "Default")
      (node (ref "U$1") (pin "AD2") (pinfunction "1_AD2") (pintype "bidirectional"))
    )
    (net (code "188") (name "unconnected-(U$1I-1-PadAE1)") (class "Default")
      (node (ref "U$1") (pin "AE1") (pinfunction "1_AE1") (pintype "bidirectional"))
    )
    (net (code "189") (name "unconnected-(U$1J-1-PadAE2)") (class "Default")
      (node (ref "U$1") (pin "AE2") (pinfunction "1_AE2") (pintype "bidirectional"))
    )
    (net (code "190") (name "unconnected-(U$1M-1-PadAH1)") (class "Default")
      (node (ref "U$1") (pin "AH1") (pinfunction "1_AH1") (pintype "bidirectional"))
    )
    (net (code "191") (name "unconnected-(U$1N-1-PadAH2)") (class "Default")
      (node (ref "U$1") (pin "AH2") (pinfunction "1_AH2") (pintype "bidirectional"))
    )
    (net (code "192") (name "unconnected-(U$1O-1-PadAJ1)") (class "Default")
      (node (ref "U$1") (pin "AJ1") (pinfunction "1_AJ1") (pintype "bidirectional"))
    )
    (net (code "193") (name "unconnected-(U$1P-1-PadAJ2)") (class "Default")
      (node (ref "U$1") (pin "AJ2") (pinfunction "1_AJ2") (pintype "bidirectional"))
    )
    (net (code "194") (name "unconnected-(U$1Q-1-PadAK1)") (class "Default")
      (node (ref "U$1") (pin "AK1") (pinfunction "1_AK1") (pintype "bidirectional"))
    )
    (net (code "195") (name "unconnected-(U$1R-1-PadAK2)") (class "Default")
      (node (ref "U$1") (pin "AK2") (pinfunction "1_AK2") (pintype "bidirectional"))
    )
    (net (code "196") (name "unconnected-(U$1S-1-PadAL1)") (class "Default")
      (node (ref "U$1") (pin "AL1") (pinfunction "1_AL1") (pintype "bidirectional"))
    )
    (net (code "197") (name "unconnected-(U$1T-1-PadAL2)") (class "Default")
      (node (ref "U$1") (pin "AL2") (pinfunction "1_AL2") (pintype "bidirectional"))
    )
    (net (code "198") (name "unconnected-(U$1U-1-PadAM1)") (class "Default")
      (node (ref "U$1") (pin "AM1") (pinfunction "1_AM1") (pintype "bidirectional"))
    )
    (net (code "199") (name "unconnected-(U$1V-1-PadAM2)") (class "Default")
      (node (ref "U$1") (pin "AM2") (pinfunction "1_AM2") (pintype "bidirectional"))
    )
    (net (code "200") (name "unconnected-(U$1Z-1-PadAP2)") (class "Default")
      (node (ref "U$1") (pin "AP2") (pinfunction "1_AP2") (pintype "bidirectional"))
    )
  )
)
